# Sata.net
KiCad netlist of a schematic drawn in Altium Designer
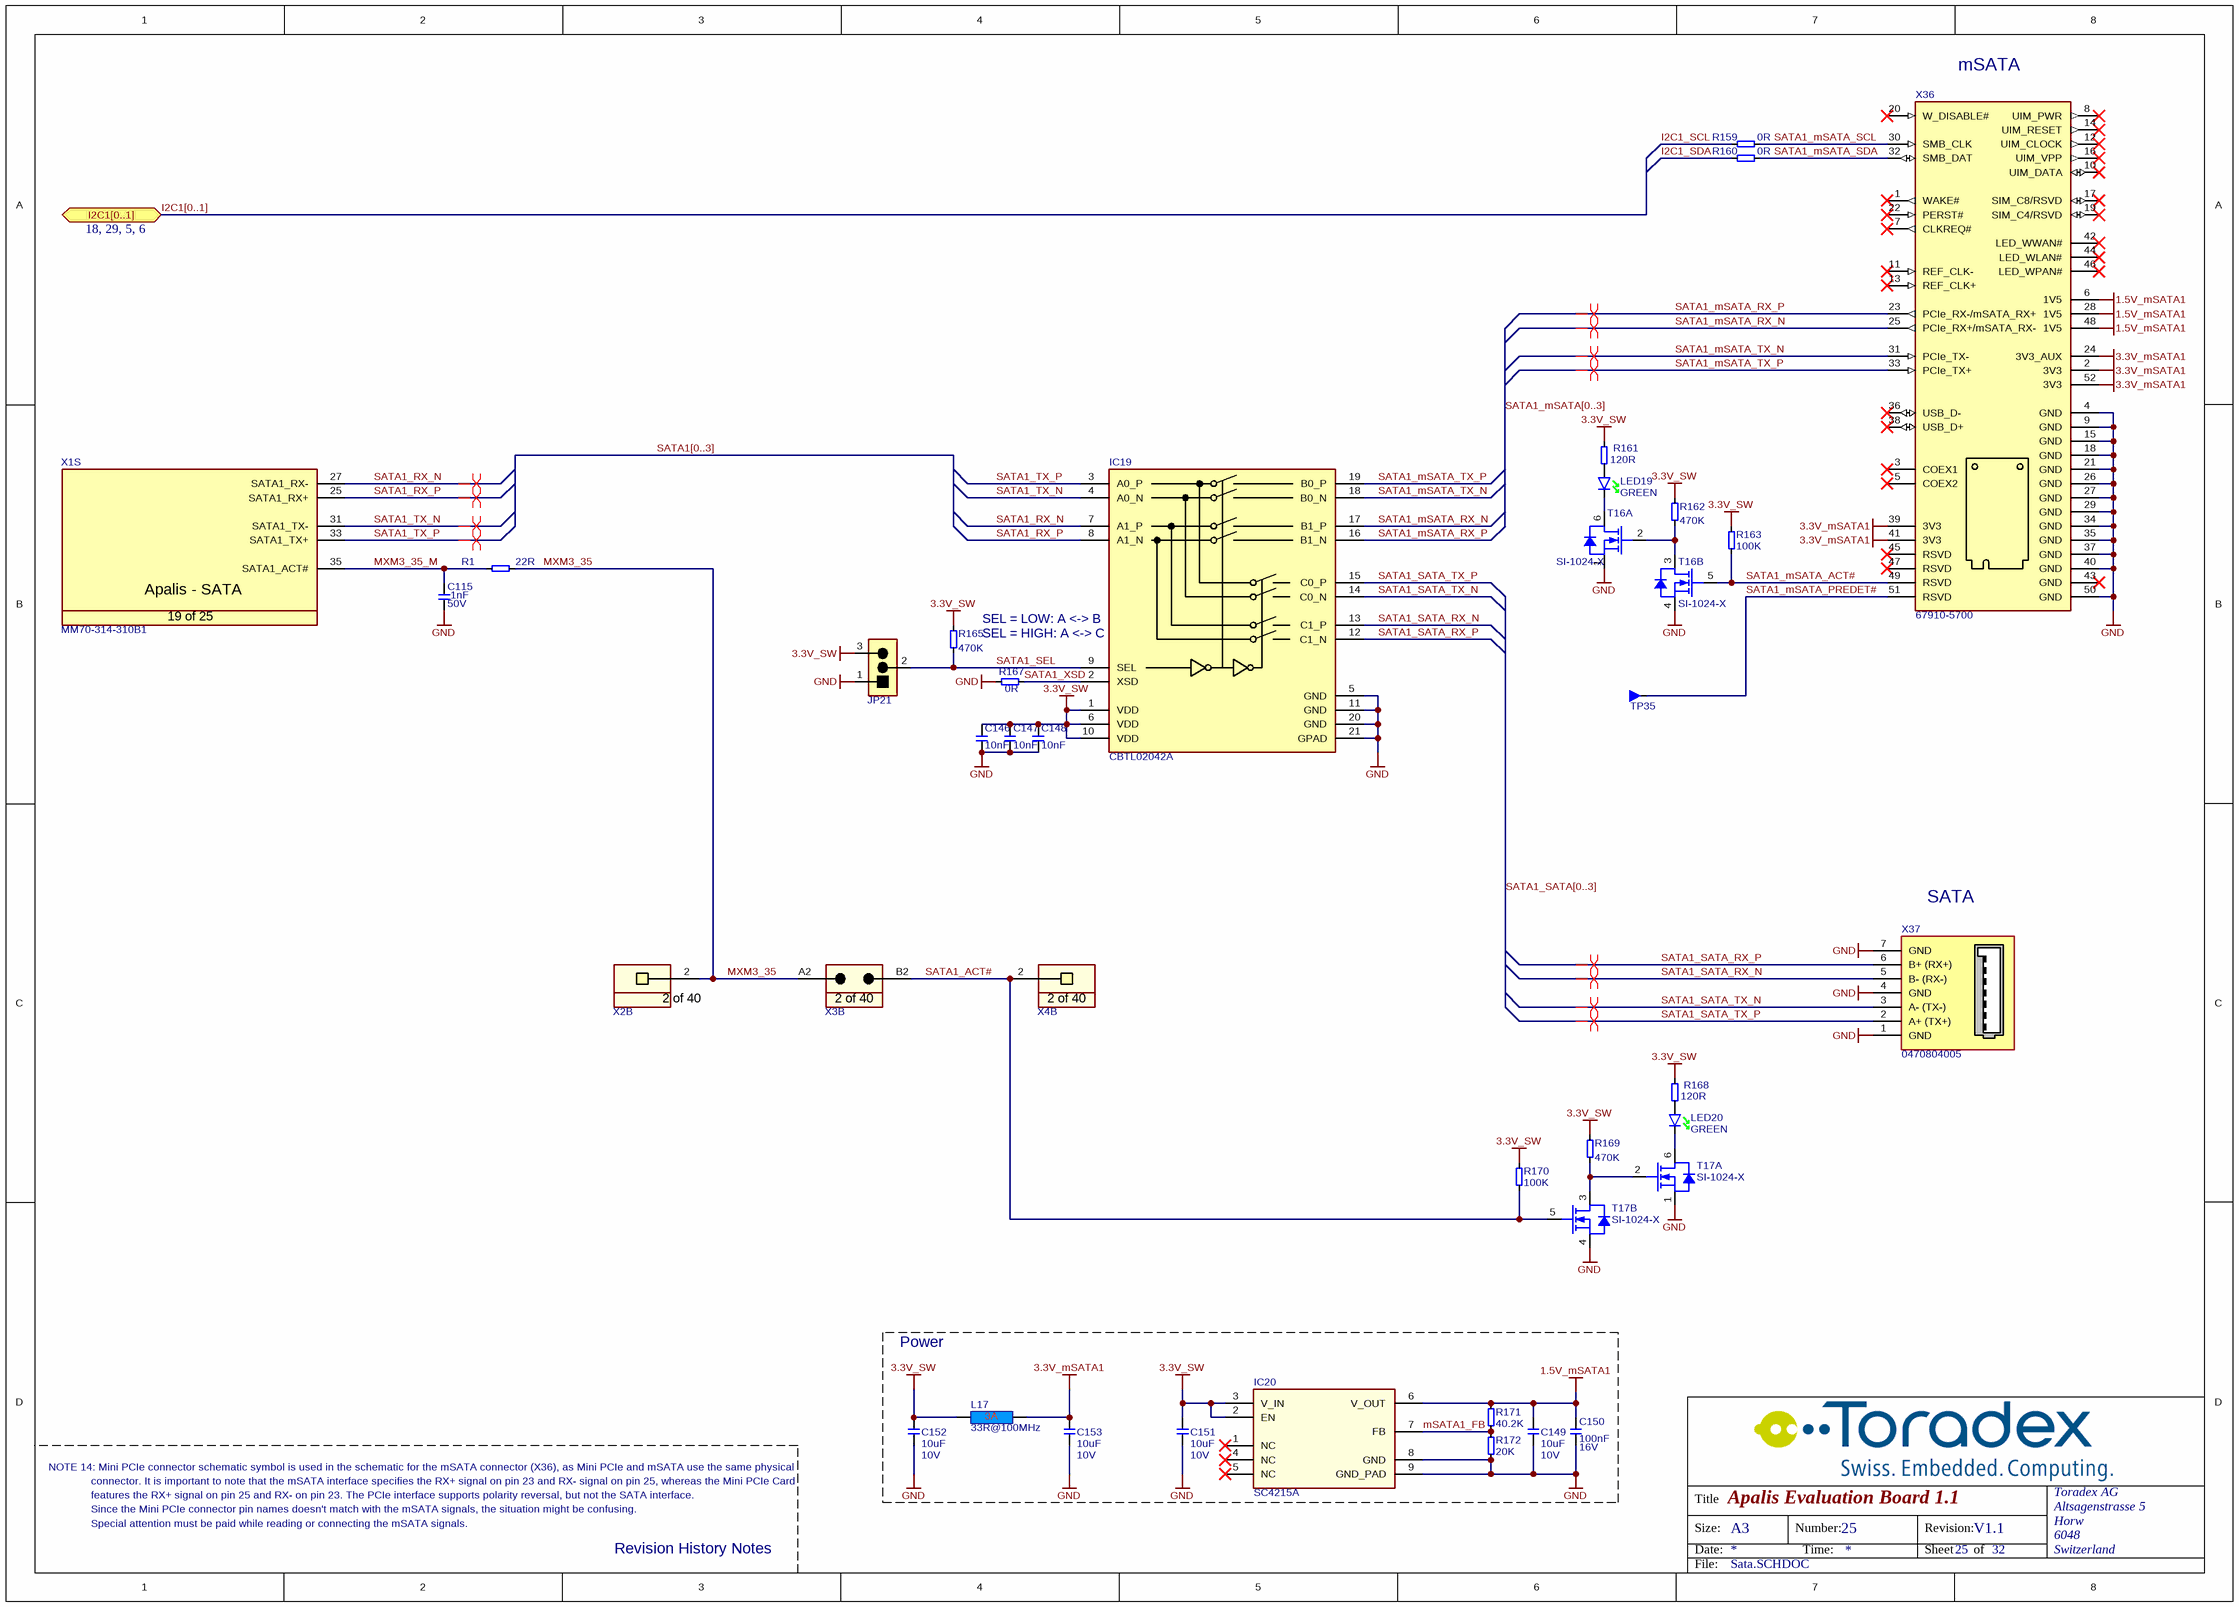
[diagram p0: Sata.SCHDOC]

(export (version "E")
  (design (tool "Eeschema 10.0.6"))
  (components
    (comp (ref "C115")
      (value "1nF")
      (footprint "CAPC1005X60N")
      (description "Capacitor Ceramic X7R 1nF 50V 10% 0402")
      (fields (field (name "TOLERANCE") "10%") (field (name "RATING") "50V"))
      (libsource (lib "Apalis Evaluation Board") (part "C-X7R-1nF-50V-10%-0402"))
    )
    (comp (ref "C146")
      (value "10nF")
      (footprint "T_CAPC0603X33N")
      (description "Capacitor Ceramic X7R 10nF 25V 10% 0603")
      (fields (field (name "TOLERANCE") "10%"))
      (libsource (lib "Apalis Evaluation Board") (part "C-X7R-10nF-25V-10%-0603"))
    )
    (comp (ref "C147")
      (value "10nF")
      (footprint "T_CAPC0603X33N")
      (description "Capacitor Ceramic X7R 10nF 25V 10% 0603")
      (fields (field (name "TOLERANCE") "10%"))
      (libsource (lib "Apalis Evaluation Board") (part "C-X7R-10nF-25V-10%-0603"))
    )
    (comp (ref "C148")
      (value "10nF")
      (footprint "T_CAPC0603X33N")
      (description "Capacitor Ceramic X7R 10nF 25V 10% 0603")
      (fields (field (name "TOLERANCE") "10%"))
      (libsource (lib "Apalis Evaluation Board") (part "C-X7R-10nF-25V-10%-0603"))
    )
    (comp (ref "C149")
      (value "10uF")
      (footprint "T_CAPC0603X33N")
      (description "Capacitor Ceramic X5R 10uF 10V 20% 0603")
      (fields (field (name "TOLERANCE") "20%") (field (name "RATING") "10V"))
      (libsource (lib "Apalis Evaluation Board") (part "C-X5R-10uF-10V-20%-0603"))
    )
    (comp (ref "C150")
      (value "100nF")
      (footprint "T_CAPC0603X33N")
      (description "Capacitor Ceramic X7R 100nF 16V 10% 0603")
      (fields (field (name "TOLERANCE") "10%") (field (name "RATING") "16V"))
      (libsource (lib "Apalis Evaluation Board") (part "C-X7R-100nF-16V-10%-0603"))
    )
    (comp (ref "C151")
      (value "10uF")
      (footprint "T_CAPC0603X33N")
      (description "Capacitor Ceramic X5R 10uF 10V 20% 0603")
      (fields (field (name "TOLERANCE") "20%") (field (name "RATING") "10V"))
      (libsource (lib "Apalis Evaluation Board") (part "C-X5R-10uF-10V-20%-0603"))
    )
    (comp (ref "C152")
      (value "10uF")
      (footprint "T_CAPC0603X33N")
      (description "Capacitor Ceramic X5R 10uF 10V 20% 0603")
      (fields (field (name "TOLERANCE") "20%") (field (name "RATING") "10V"))
      (libsource (lib "Apalis Evaluation Board") (part "C-X5R-10uF-10V-20%-0603"))
    )
    (comp (ref "C153")
      (value "10uF")
      (footprint "T_CAPC0603X33N")
      (description "Capacitor Ceramic X5R 10uF 10V 20% 0603")
      (fields (field (name "TOLERANCE") "20%") (field (name "RATING") "10V"))
      (libsource (lib "Apalis Evaluation Board") (part "C-X5R-10uF-10V-20%-0603"))
    )
    (comp (ref "IC19")
      (value "CBTL02042A")
      (footprint "QFN50P250X450X100-20N")
      (description "Analog Switch CBTL02042A")
      (fields (field (name "MANUFACTURER PART NO.") "CBTL02042A"))
      (libsource (lib "Apalis Evaluation Board") (part "IC-NXP-CBTL02042A"))
    )
    (comp (ref "IC20")
      (value "IC-Semtech-SC4215A")
      (footprint "SOIC127P650X175_HS-8N")
      (description "LDO TO 2A")
      (fields (field (name "PART NO.") "SC4215A"))
      (libsource (lib "Apalis Evaluation Board") (part "IC-Semtech-SC4215A"))
    )
    (comp (ref "JP21")
      (value "826936-3")
      (footprint "T_TYCO_826936-3")
      (description "Jumper, 3-Pin")
      (libsource (lib "Apalis Evaluation Board") (part "CON-Tyco-826936-3-1X3-2.54mm-JP_1"))
    )
    (comp (ref "L17")
      (value "33R@100MHz")
      (footprint "INDC1608X95N")
      (description "33R@100MHz 3A EMI FILTER")
      (fields (field (name "TOLERANCE") "25%"))
      (libsource (lib "Apalis Evaluation Board") (part "L-33R@100MHz-3A-25%-0603"))
    )
    (comp (ref "LED19")
      (value "LG T670-K1L2-1")
      (footprint "T_Osram_T670_GREEN")
      (description "LED green Osram LG T670-K1L2-1")
      (fields (field (name "COLOR") "GREEN"))
      (libsource (lib "Apalis Evaluation Board") (part "LED-Osram-T670-K1L2-1"))
    )
    (comp (ref "LED20")
      (value "LG T670-K1L2-1")
      (footprint "T_Osram_T670_GREEN")
      (description "LED green Osram LG T670-K1L2-1")
      (fields (field (name "COLOR") "GREEN"))
      (libsource (lib "Apalis Evaluation Board") (part "LED-Osram-T670-K1L2-1"))
    )
    (comp (ref "R1")
      (value "22R")
      (footprint "RESC1005X40N")
      (description "Resistor 22 ohm 63mW 5% 0402")
      (fields (field (name "TOLERANCE") "5%"))
      (libsource (lib "Apalis Evaluation Board") (part "R-22R-63mW-5%-0402"))
    )
    (comp (ref "R159")
      (value "0R")
      (footprint "T_RESC0603X30N")
      (description "Resistor 0 ohm 63mW 1% 0603")
      (fields (field (name "TOLERANCE") "1%"))
      (libsource (lib "Apalis Evaluation Board") (part "R-0R-63mW-1%-0603"))
    )
    (comp (ref "R160")
      (value "0R")
      (footprint "T_RESC0603X30N")
      (description "Resistor 0 ohm 63mW 1% 0603")
      (fields (field (name "TOLERANCE") "1%"))
      (libsource (lib "Apalis Evaluation Board") (part "R-0R-63mW-1%-0603"))
    )
    (comp (ref "R161")
      (value "120R")
      (footprint "T_RESC0603X30N")
      (description "Resistor 120 ohm 63mW 5% 0603")
      (fields (field (name "TOLERANCE") "5%"))
      (libsource (lib "Apalis Evaluation Board") (part "R-120R-63mW-5%-0603"))
    )
    (comp (ref "R162")
      (value "470K")
      (footprint "T_RESC0603X30N")
      (description "Resistor 470 Kohm 63mW 5% 0603")
      (fields (field (name "TOLERANCE") "5%"))
      (libsource (lib "Apalis Evaluation Board") (part "R-470KR-63mW-5%-0603"))
    )
    (comp (ref "R163")
      (value "100K")
      (footprint "T_RESC0603X30N")
      (description "Resistor 100 Kohm 63mW 5% 0603")
      (fields (field (name "TOLERANCE") "5%"))
      (libsource (lib "Apalis Evaluation Board") (part "R-100KR-63mW-5%-0603"))
    )
    (comp (ref "R165")
      (value "470K")
      (footprint "T_RESC0603X30N")
      (description "Resistor 470 Kohm 63mW 5% 0603")
      (fields (field (name "TOLERANCE") "5%"))
      (libsource (lib "Apalis Evaluation Board") (part "R-470KR-63mW-5%-0603"))
    )
    (comp (ref "R167")
      (value "0R")
      (footprint "T_RESC0603X30N")
      (description "Resistor 0 ohm 63mW 1% 0603")
      (fields (field (name "TOLERANCE") "1%"))
      (libsource (lib "Apalis Evaluation Board") (part "R-0R-63mW-1%-0603"))
    )
    (comp (ref "R168")
      (value "120R")
      (footprint "T_RESC0603X30N")
      (description "Resistor 120 ohm 63mW 5% 0603")
      (fields (field (name "TOLERANCE") "5%"))
      (libsource (lib "Apalis Evaluation Board") (part "R-120R-63mW-5%-0603"))
    )
    (comp (ref "R169")
      (value "470K")
      (footprint "T_RESC0603X30N")
      (description "Resistor 470 Kohm 63mW 5% 0603")
      (fields (field (name "TOLERANCE") "5%"))
      (libsource (lib "Apalis Evaluation Board") (part "R-470KR-63mW-5%-0603"))
    )
    (comp (ref "R170")
      (value "100K")
      (footprint "T_RESC0603X30N")
      (description "Resistor 100 Kohm 63mW 5% 0603")
      (fields (field (name "TOLERANCE") "5%"))
      (libsource (lib "Apalis Evaluation Board") (part "R-100KR-63mW-5%-0603"))
    )
    (comp (ref "R171")
      (value "40.2K")
      (footprint "T_RESC0603X30N")
      (description "Resistor 40.2 Kohm 63mW 1% 0603")
      (fields (field (name "TOLERANCE") "1%"))
      (libsource (lib "Apalis Evaluation Board") (part "R-40.2KR-63mW-1%-0603"))
    )
    (comp (ref "R172")
      (value "20K")
      (footprint "T_RESC0603X30N")
      (description "Resistor 20 Kohm 63mW 1% 0603")
      (fields (field (name "TOLERANCE") "1%"))
      (libsource (lib "Apalis Evaluation Board") (part "R-20KR-63mW-1%-0603"))
    )
    (comp (ref "T16")
      (value "T-Vishay-SI-1024X-N")
      (footprint "SOTFL50P160X60-6N")
      (description "Dual N-Channel 20V (D-S)  MOSFET")
      (fields (field (name "MANUFACTURER PART NO.") "SI-1024-X"))
      (libsource (lib "Apalis Evaluation Board") (part "T-Vishay-SI-1024X-N"))
    )
    (comp (ref "T17")
      (value "T-Vishay-SI-1024X-N")
      (footprint "SOTFL50P160X60-6N")
      (description "Dual N-Channel 20V (D-S)  MOSFET")
      (fields (field (name "MANUFACTURER PART NO.") "SI-1024-X"))
      (libsource (lib "Apalis Evaluation Board") (part "T-Vishay-SI-1024X-N"))
    )
    (comp (ref "TP35")
      (value "Testpin")
      (footprint "T_TP-THT")
      (description "Testpin TH")
      (libsource (lib "Apalis Evaluation Board") (part "Testpin"))
    )
    (comp (ref "X1")
      (value "CON-JAE-MM70-314-310B1-314-0.5mm")
      (footprint "T_JAE_MM70-314-310B1")
      (description "MXM3 Connector")
      (fields (field (name "MANUFACTURER PART NO.") "MM70-314-310B1"))
      (libsource (lib "Apalis Evaluation Board") (part "CON-JAE-MM70-314-310B1-314-0.5mm"))
    )
    (comp (ref "X2")
      (value "SSW-110-01-G-S")
      (footprint "T_Samtec_SSW-110-01-G-S")
      (description "Receptacle Female Socket 1x40 pin 2.54mm pitch")
      (libsource (lib "") (part "CON-Samtec-SSW-110-01-G-S_1"))
    )
    (comp (ref "X3")
      (value "TSW-110-07-G-D")
      (footprint "T_Samtec_TSW-110-07-G-D")
      (description "Header 2x40 pin 2.54mm pitch")
      (libsource (lib "Apalis Evaluation Board") (part "CON-Samtec-TSW-110-07-G-D"))
    )
    (comp (ref "X4")
      (value "SSW-110-01-G-S")
      (footprint "T_Samtec_SSW-110-01-G-S")
      (description "Receptacle Female Socket 1x40 pin 2.54mm pitch")
      (libsource (lib "Apalis Evaluation Board") (part "CON-Samtec-SSW-110-01-G-S"))
    )
    (comp (ref "X36")
      (value "67910-5700")
      (footprint "T_Molex_67910-5700")
      (description "PCIe_Mini Card Holder")
      (fields (field (name "PART NO.") "67910-5700"))
      (libsource (lib "Apalis Evaluation Board") (part "CON-Molex-67910-5700"))
    )
    (comp (ref "X37")
      (value "0470804005")
      (footprint "T_Molex_47080-4005")
      (description "Sata Plugr SMD")
      (fields (field (name "MANUFACTURER PART NO.") "47080-4005"))
      (libsource (lib "Apalis Evaluation Board") (part "CON-Molex-047080-4005"))
    )
  )
  (nets
    (net (code "16") (name "/I2C1_SCL") (class "Default")
      (node (ref "R159") (pin "1") (pinfunction "1_1") (pintype "passive"))
    )
    (net (code "17") (name "/I2C1_SDA") (class "Default")
      (node (ref "R160") (pin "1") (pinfunction "1_1") (pintype "passive"))
    )
    (net (code "18") (name "/MXM3_35") (class "Default")
      (node (ref "R1") (pin "2") (pinfunction "2_2") (pintype "passive"))
      (node (ref "X2") (pin "2") (pinfunction "2_2") (pintype "passive"))
      (node (ref "X3") (pin "A2") (pinfunction "A2_A2") (pintype "passive"))
    )
    (net (code "19") (name "/MXM3_35_M") (class "Default")
      (node (ref "C115") (pin "2") (pinfunction "2_2") (pintype "passive"))
      (node (ref "R1") (pin "1") (pinfunction "1_1") (pintype "passive"))
      (node (ref "X1") (pin "35") (pinfunction "SATA1_ACT#_35") (pintype "passive"))
    )
    (net (code "21") (name "/SATA1_ACT#") (class "Default")
      (node (ref "R170") (pin "1") (pinfunction "1_1") (pintype "passive"))
      (node (ref "T17") (pin "5") (pinfunction "G_5") (pintype "passive"))
      (node (ref "X3") (pin "B2") (pinfunction "B2_B2") (pintype "passive"))
      (node (ref "X4") (pin "2") (pinfunction "2_2") (pintype "passive"))
    )
    (net (code "22") (name "/SATA1_RX_N") (class "Default")
      (node (ref "IC19") (pin "7") (pinfunction "A1_P_7") (pintype "passive"))
      (node (ref "X1") (pin "27") (pinfunction "SATA1_RX-_27") (pintype "passive"))
    )
    (net (code "23") (name "/SATA1_RX_P") (class "Default")
      (node (ref "IC19") (pin "8") (pinfunction "A1_N_8") (pintype "passive"))
      (node (ref "X1") (pin "25") (pinfunction "SATA1_RX+_25") (pintype "passive"))
    )
    (net (code "25") (name "/SATA1_SATA_RX_N") (class "Default")
      (node (ref "IC19") (pin "13") (pinfunction "C1_P_13") (pintype "passive"))
      (node (ref "X37") (pin "5") (pinfunction "B-_(RX-)_5") (pintype "passive"))
    )
    (net (code "26") (name "/SATA1_SATA_RX_P") (class "Default")
      (node (ref "IC19") (pin "12") (pinfunction "C1_N_12") (pintype "passive"))
      (node (ref "X37") (pin "6") (pinfunction "B+_(RX+)_6") (pintype "passive"))
    )
    (net (code "27") (name "/SATA1_SATA_TX_N") (class "Default")
      (node (ref "IC19") (pin "14") (pinfunction "C0_N_14") (pintype "passive"))
      (node (ref "X37") (pin "3") (pinfunction "A-_(TX-)_3") (pintype "passive"))
    )
    (net (code "28") (name "/SATA1_SATA_TX_P") (class "Default")
      (node (ref "IC19") (pin "15") (pinfunction "C0_P_15") (pintype "passive"))
      (node (ref "X37") (pin "2") (pinfunction "A+_(TX+)_2") (pintype "passive"))
    )
    (net (code "29") (name "/SATA1_SEL") (class "Default")
      (node (ref "IC19") (pin "9") (pinfunction "SEL_9") (pintype "passive"))
      (node (ref "JP21") (pin "2") (pinfunction "2_2") (pintype "passive"))
      (node (ref "R165") (pin "2") (pinfunction "2_2") (pintype "passive"))
    )
    (net (code "30") (name "/SATA1_TX_N") (class "Default")
      (node (ref "IC19") (pin "4") (pinfunction "A0_N_4") (pintype "passive"))
      (node (ref "X1") (pin "31") (pinfunction "SATA1_TX-_31") (pintype "passive"))
    )
    (net (code "31") (name "/SATA1_TX_P") (class "Default")
      (node (ref "IC19") (pin "3") (pinfunction "A0_P_3") (pintype "passive"))
      (node (ref "X1") (pin "33") (pinfunction "SATA1_TX+_33") (pintype "passive"))
    )
    (net (code "32") (name "/SATA1_XSD") (class "Default")
      (node (ref "IC19") (pin "2") (pinfunction "XSD_2") (pintype "passive"))
      (node (ref "R167") (pin "2") (pinfunction "2_2") (pintype "passive"))
    )
    (net (code "34") (name "/SATA1_mSATA_ACT#") (class "Default")
      (node (ref "R163") (pin "1") (pinfunction "1_1") (pintype "passive"))
      (node (ref "T16") (pin "5") (pinfunction "G_5") (pintype "passive"))
      (node (ref "X36") (pin "49") (pinfunction "RSVD_49") (pintype "passive"))
    )
    (net (code "35") (name "/SATA1_mSATA_PREDET#") (class "Default")
      (node (ref "TP35") (pin "1") (pinfunction "1_1") (pintype "passive"))
      (node (ref "X36") (pin "51") (pinfunction "RSVD_51") (pintype "passive"))
    )
    (net (code "36") (name "/SATA1_mSATA_RX_N") (class "Default")
      (node (ref "IC19") (pin "17") (pinfunction "B1_P_17") (pintype "passive"))
      (node (ref "X36") (pin "25") (pinfunction "PCIe_RX+/mSATA_RX-_25") (pintype "output"))
    )
    (net (code "37") (name "/SATA1_mSATA_RX_P") (class "Default")
      (node (ref "IC19") (pin "16") (pinfunction "B1_N_16") (pintype "passive"))
      (node (ref "X36") (pin "23") (pinfunction "PCIe_RX-/mSATA_RX+_23") (pintype "output"))
    )
    (net (code "38") (name "/SATA1_mSATA_SCL") (class "Default")
      (node (ref "R159") (pin "2") (pinfunction "2_2") (pintype "passive"))
      (node (ref "X36") (pin "30") (pinfunction "SMB_CLK_30") (pintype "input"))
    )
    (net (code "39") (name "/SATA1_mSATA_SDA") (class "Default")
      (node (ref "R160") (pin "2") (pinfunction "2_2") (pintype "passive"))
      (node (ref "X36") (pin "32") (pinfunction "SMB_DAT_32") (pintype "bidirectional"))
    )
    (net (code "40") (name "/SATA1_mSATA_TX_N") (class "Default")
      (node (ref "IC19") (pin "18") (pinfunction "B0_N_18") (pintype "passive"))
      (node (ref "X36") (pin "31") (pinfunction "PCIe_TX-_31") (pintype "input"))
    )
    (net (code "41") (name "/SATA1_mSATA_TX_P") (class "Default")
      (node (ref "IC19") (pin "19") (pinfunction "B0_P_19") (pintype "passive"))
      (node (ref "X36") (pin "33") (pinfunction "PCIe_TX+_33") (pintype "input"))
    )
    (net (code "42") (name "/mSATA1_FB") (class "Default")
      (node (ref "IC20") (pin "7") (pinfunction "FB_7") (pintype "passive"))
      (node (ref "R171") (pin "1") (pinfunction "1_1") (pintype "passive"))
      (node (ref "R172") (pin "2") (pinfunction "2_2") (pintype "passive"))
    )
    (net (code "43") (name "1.5V_mSATA1") (class "Default")
      (node (ref "C149") (pin "2") (pinfunction "2_2") (pintype "passive"))
      (node (ref "C150") (pin "2") (pinfunction "2_2") (pintype "passive"))
      (node (ref "IC20") (pin "6") (pinfunction "V_OUT_6") (pintype "passive"))
      (node (ref "R171") (pin "2") (pinfunction "2_2") (pintype "passive"))
      (node (ref "X36") (pin "28") (pinfunction "1V5_28") (pintype "power_in"))
      (node (ref "X36") (pin "48") (pinfunction "1V5_48") (pintype "power_in"))
      (node (ref "X36") (pin "6") (pinfunction "1V5_6") (pintype "power_in"))
    )
    (net (code "44") (name "3.3V_SW") (class "Default")
      (node (ref "C146") (pin "2") (pinfunction "2_2") (pintype "passive"))
      (node (ref "C147") (pin "2") (pinfunction "2_2") (pintype "passive"))
      (node (ref "C148") (pin "2") (pinfunction "2_2") (pintype "passive"))
      (node (ref "C151") (pin "2") (pinfunction "2_2") (pintype "passive"))
      (node (ref "C152") (pin "2") (pinfunction "2_2") (pintype "passive"))
      (node (ref "IC19") (pin "1") (pinfunction "VDD_1") (pintype "passive"))
      (node (ref "IC19") (pin "10") (pinfunction "VDD_10") (pintype "passive"))
      (node (ref "IC19") (pin "6") (pinfunction "VDD_6") (pintype "passive"))
      (node (ref "IC20") (pin "2") (pinfunction "EN_2") (pintype "passive"))
      (node (ref "IC20") (pin "3") (pinfunction "V_IN_3") (pintype "passive"))
      (node (ref "JP21") (pin "3") (pinfunction "3_3") (pintype "passive"))
      (node (ref "L17") (pin "1") (pinfunction "1_1") (pintype "passive"))
      (node (ref "R161") (pin "2") (pinfunction "2_2") (pintype "passive"))
      (node (ref "R162") (pin "1") (pinfunction "1_1") (pintype "passive"))
      (node (ref "R163") (pin "2") (pinfunction "2_2") (pintype "passive"))
      (node (ref "R165") (pin "1") (pinfunction "1_1") (pintype "passive"))
      (node (ref "R168") (pin "2") (pinfunction "2_2") (pintype "passive"))
      (node (ref "R169") (pin "1") (pinfunction "1_1") (pintype "passive"))
      (node (ref "R170") (pin "2") (pinfunction "2_2") (pintype "passive"))
    )
    (net (code "45") (name "3.3V_mSATA1") (class "Default")
      (node (ref "C153") (pin "2") (pinfunction "2_2") (pintype "passive"))
      (node (ref "L17") (pin "2") (pinfunction "2_2") (pintype "passive"))
      (node (ref "X36") (pin "2") (pinfunction "3V3_2") (pintype "power_in"))
      (node (ref "X36") (pin "24") (pinfunction "3V3_AUX_24") (pintype "power_in"))
      (node (ref "X36") (pin "39") (pinfunction "3V3_39") (pintype "passive"))
      (node (ref "X36") (pin "41") (pinfunction "3V3_41") (pintype "passive"))
      (node (ref "X36") (pin "52") (pinfunction "3V3_52") (pintype "power_in"))
    )
    (net (code "46") (name "GND") (class "Default")
      (node (ref "C115") (pin "1") (pinfunction "1_1") (pintype "passive"))
      (node (ref "C146") (pin "1") (pinfunction "1_1") (pintype "passive"))
      (node (ref "C147") (pin "1") (pinfunction "1_1") (pintype "passive"))
      (node (ref "C148") (pin "1") (pinfunction "1_1") (pintype "passive"))
      (node (ref "C149") (pin "1") (pinfunction "1_1") (pintype "passive"))
      (node (ref "C150") (pin "1") (pinfunction "1_1") (pintype "passive"))
      (node (ref "C151") (pin "1") (pinfunction "1_1") (pintype "passive"))
      (node (ref "C152") (pin "1") (pinfunction "1_1") (pintype "passive"))
      (node (ref "C153") (pin "1") (pinfunction "1_1") (pintype "passive"))
      (node (ref "IC19") (pin "11") (pinfunction "GND_11") (pintype "passive"))
      (node (ref "IC19") (pin "20") (pinfunction "GND_20") (pintype "passive"))
      (node (ref "IC19") (pin "21") (pinfunction "GPAD_21") (pintype "passive"))
      (node (ref "IC19") (pin "5") (pinfunction "GND_5") (pintype "passive"))
      (node (ref "IC20") (pin "8") (pinfunction "GND_8") (pintype "passive"))
      (node (ref "IC20") (pin "9") (pinfunction "GND_PAD_9") (pintype "passive"))
      (node (ref "JP21") (pin "1") (pinfunction "1_1") (pintype "passive"))
      (node (ref "R167") (pin "1") (pinfunction "1_1") (pintype "passive"))
      (node (ref "R172") (pin "1") (pinfunction "1_1") (pintype "passive"))
      (node (ref "T16") (pin "1") (pinfunction "S_1") (pintype "passive"))
      (node (ref "T16") (pin "4") (pinfunction "S_4") (pintype "passive"))
      (node (ref "T17") (pin "1") (pinfunction "S_1") (pintype "passive"))
      (node (ref "T17") (pin "4") (pinfunction "S_4") (pintype "passive"))
      (node (ref "X36") (pin "15") (pinfunction "GND_15") (pintype "power_in"))
      (node (ref "X36") (pin "18") (pinfunction "GND_18") (pintype "power_in"))
      (node (ref "X36") (pin "21") (pinfunction "GND_21") (pintype "power_in"))
      (node (ref "X36") (pin "26") (pinfunction "GND_26") (pintype "power_in"))
      (node (ref "X36") (pin "27") (pinfunction "GND_27") (pintype "power_in"))
      (node (ref "X36") (pin "29") (pinfunction "GND_29") (pintype "power_in"))
      (node (ref "X36") (pin "34") (pinfunction "GND_34") (pintype "power_in"))
      (node (ref "X36") (pin "35") (pinfunction "GND_35") (pintype "power_in"))
      (node (ref "X36") (pin "37") (pinfunction "GND_37") (pintype "power_in"))
      (node (ref "X36") (pin "4") (pinfunction "GND_4") (pintype "power_in"))
      (node (ref "X36") (pin "40") (pinfunction "GND_40") (pintype "power_in"))
      (node (ref "X36") (pin "50") (pinfunction "GND_50") (pintype "power_in"))
      (node (ref "X36") (pin "9") (pinfunction "GND_9") (pintype "power_in"))
      (node (ref "X37") (pin "1") (pinfunction "GND_1") (pintype "power_in"))
      (node (ref "X37") (pin "4") (pinfunction "GND_4") (pintype "power_in"))
      (node (ref "X37") (pin "7") (pinfunction "GND_7") (pintype "power_in"))
    )
    (net (code "47") (name "Net-(LED19-PadA)") (class "Default")
      (node (ref "LED19") (pin "A") (pinfunction "A_A") (pintype "passive"))
      (node (ref "R161") (pin "1") (pinfunction "1_1") (pintype "passive"))
    )
    (net (code "48") (name "Net-(LED20-PadA)") (class "Default")
      (node (ref "LED20") (pin "A") (pinfunction "A_A") (pintype "passive"))
      (node (ref "R168") (pin "1") (pinfunction "1_1") (pintype "passive"))
    )
    (net (code "49") (name "Net-(T16A-D)") (class "Default")
      (node (ref "LED19") (pin "K") (pinfunction "K_K") (pintype "passive"))
      (node (ref "T16") (pin "6") (pinfunction "D_6") (pintype "passive"))
    )
    (net (code "50") (name "Net-(T16A-G)") (class "Default")
      (node (ref "R162") (pin "2") (pinfunction "2_2") (pintype "passive"))
      (node (ref "T16") (pin "2") (pinfunction "G_2") (pintype "passive"))
      (node (ref "T16") (pin "3") (pinfunction "D_3") (pintype "passive"))
    )
    (net (code "51") (name "Net-(T17A-D)") (class "Default")
      (node (ref "LED20") (pin "K") (pinfunction "K_K") (pintype "passive"))
      (node (ref "T17") (pin "6") (pinfunction "D_6") (pintype "passive"))
    )
    (net (code "52") (name "Net-(T17A-G)") (class "Default")
      (node (ref "R169") (pin "2") (pinfunction "2_2") (pintype "passive"))
      (node (ref "T17") (pin "2") (pinfunction "G_2") (pintype "passive"))
      (node (ref "T17") (pin "3") (pinfunction "D_3") (pintype "passive"))
    )
    (net (code "53") (name "unconnected-(IC20-NC-Pad1)") (class "Default")
      (node (ref "IC20") (pin "1") (pinfunction "NC_1") (pintype "passive+no_connect"))
    )
    (net (code "54") (name "unconnected-(IC20-NC-Pad4)") (class "Default")
      (node (ref "IC20") (pin "4") (pinfunction "NC_4") (pintype "passive+no_connect"))
    )
    (net (code "55") (name "unconnected-(IC20-NC-Pad5)") (class "Default")
      (node (ref "IC20") (pin "5") (pinfunction "NC_5") (pintype "passive+no_connect"))
    )
    (net (code "56") (name "unconnected-(X36-CLKREQ#-Pad7)") (class "Default")
      (node (ref "X36") (pin "7") (pinfunction "CLKREQ#_7") (pintype "output+no_connect"))
    )
    (net (code "57") (name "unconnected-(X36-COEX1-Pad3)") (class "Default")
      (node (ref "X36") (pin "3") (pinfunction "COEX1_3") (pintype "passive+no_connect"))
    )
    (net (code "58") (name "unconnected-(X36-COEX2-Pad5)") (class "Default")
      (node (ref "X36") (pin "5") (pinfunction "COEX2_5") (pintype "passive+no_connect"))
    )
    (net (code "59") (name "unconnected-(X36-GND-Pad43)") (class "Default")
      (node (ref "X36") (pin "43") (pinfunction "GND_43") (pintype "power_in+no_connect"))
    )
    (net (code "60") (name "unconnected-(X36-LED_WLAN#-Pad44)") (class "Default")
      (node (ref "X36") (pin "44") (pinfunction "LED_WLAN#_44") (pintype "open_collector+no_connect"))
    )
    (net (code "61") (name "unconnected-(X36-LED_WPAN#-Pad46)") (class "Default")
      (node (ref "X36") (pin "46") (pinfunction "LED_WPAN#_46") (pintype "open_collector+no_connect"))
    )
    (net (code "62") (name "unconnected-(X36-LED_WWAN#-Pad42)") (class "Default")
      (node (ref "X36") (pin "42") (pinfunction "LED_WWAN#_42") (pintype "open_collector+no_connect"))
    )
    (net (code "63") (name "unconnected-(X36-PERST#-Pad22)") (class "Default")
      (node (ref "X36") (pin "22") (pinfunction "PERST#_22") (pintype "input+no_connect"))
    )
    (net (code "64") (name "unconnected-(X36-REF_CLK+-Pad13)") (class "Default")
      (node (ref "X36") (pin "13") (pinfunction "REF_CLK+_13") (pintype "input+no_connect"))
    )
    (net (code "65") (name "unconnected-(X36-REF_CLK--Pad11)") (class "Default")
      (node (ref "X36") (pin "11") (pinfunction "REF_CLK-_11") (pintype "input+no_connect"))
    )
    (net (code "66") (name "unconnected-(X36-RSVD-Pad45)") (class "Default")
      (node (ref "X36") (pin "45") (pinfunction "RSVD_45") (pintype "passive+no_connect"))
    )
    (net (code "67") (name "unconnected-(X36-RSVD-Pad47)") (class "Default")
      (node (ref "X36") (pin "47") (pinfunction "RSVD_47") (pintype "passive+no_connect"))
    )
    (net (code "68") (name "unconnected-(X36-SIM_C4{slash}RSVD-Pad19)") (class "Default")
      (node (ref "X36") (pin "19") (pinfunction "SIM_C4/RSVD_19") (pintype "bidirectional+no_connect"))
    )
    (net (code "69") (name "unconnected-(X36-SIM_C8{slash}RSVD-Pad17)") (class "Default")
      (node (ref "X36") (pin "17") (pinfunction "SIM_C8/RSVD_17") (pintype "bidirectional+no_connect"))
    )
    (net (code "70") (name "unconnected-(X36-UIM_CLOCK-Pad12)") (class "Default")
      (node (ref "X36") (pin "12") (pinfunction "UIM_CLOCK_12") (pintype "output+no_connect"))
    )
    (net (code "71") (name "unconnected-(X36-UIM_DATA-Pad10)") (class "Default")
      (node (ref "X36") (pin "10") (pinfunction "UIM_DATA_10") (pintype "bidirectional+no_connect"))
    )
    (net (code "72") (name "unconnected-(X36-UIM_PWR-Pad8)") (class "Default")
      (node (ref "X36") (pin "8") (pinfunction "UIM_PWR_8") (pintype "output+no_connect"))
    )
    (net (code "73") (name "unconnected-(X36-UIM_RESET-Pad14)") (class "Default")
      (node (ref "X36") (pin "14") (pinfunction "UIM_RESET_14") (pintype "output+no_connect"))
    )
    (net (code "74") (name "unconnected-(X36-UIM_VPP-Pad16)") (class "Default")
      (node (ref "X36") (pin "16") (pinfunction "UIM_VPP_16") (pintype "output+no_connect"))
    )
    (net (code "75") (name "unconnected-(X36-USB_D+-Pad38)") (class "Default")
      (node (ref "X36") (pin "38") (pinfunction "USB_D+_38") (pintype "bidirectional+no_connect"))
    )
    (net (code "76") (name "unconnected-(X36-USB_D--Pad36)") (class "Default")
      (node (ref "X36") (pin "36") (pinfunction "USB_D-_36") (pintype "bidirectional+no_connect"))
    )
    (net (code "77") (name "unconnected-(X36-WAKE#-Pad1)") (class "Default")
      (node (ref "X36") (pin "1") (pinfunction "WAKE#_1") (pintype "output+no_connect"))
    )
    (net (code "78") (name "unconnected-(X36-W_DISABLE#-Pad20)") (class "Default")
      (node (ref "X36") (pin "20") (pinfunction "W_DISABLE#_20") (pintype "input+no_connect"))
    )
  )
)
